# Input_Power.net
KiCad netlist of a schematic drawn in Altium Designer
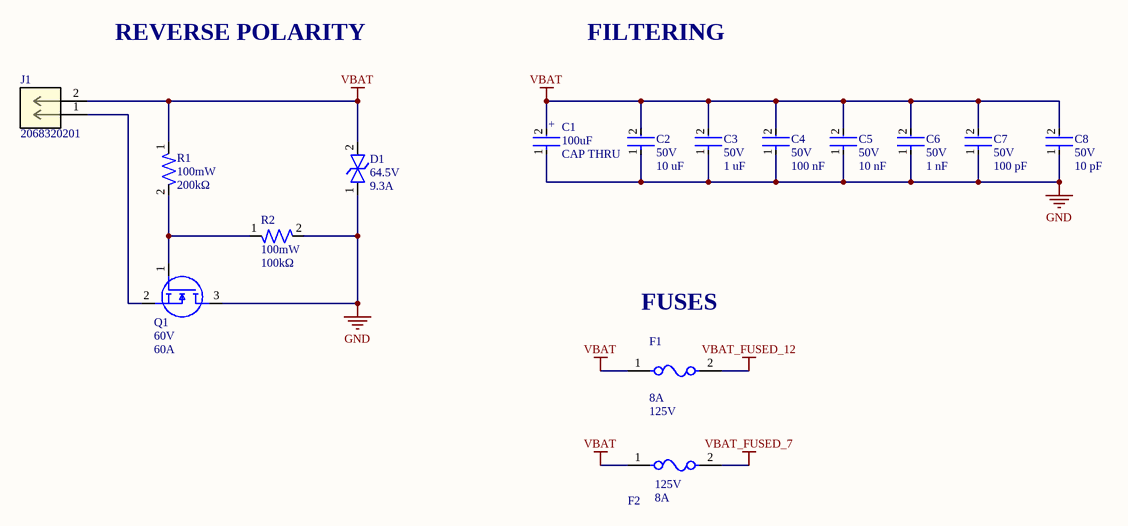
[diagram p0: Input Power.SchDoc]

(export (version "E")
  (design (tool "Eeschema 10.0.6"))
  (components
    (comp (ref "C1")
      (value "CAP THRU")
      (footprint "WCAP-ATUL_8X11.5(DXL)")
      (fields
        (field (name "MF") "{'manufacturer': u'~{W}xfcrth Elektronik'}")
        (field (name "MP") "860040674004")
        (field (name "ALTIUM_VALUE") "100uF")
      )
      (libsource (lib "EHW_27") (part "CAP THRU"))
    )
    (comp (ref "C2")
      (value "CAP 1210")
      (footprint "CAP-1210")
      (fields (field (name "VOLTAGE RATING") "50V") (field (name "CAPACITANCE") "10 uF"))
      (libsource (lib "EHW_27") (part "CAP 1210"))
    )
    (comp (ref "C3")
      (value "CAP 1210")
      (footprint "CAP-1210")
      (fields (field (name "VOLTAGE RATING") "50V") (field (name "CAPACITANCE") "1 uF"))
      (libsource (lib "EHW_27") (part "CAP 1210"))
    )
    (comp (ref "C4")
      (value "CAP 1210")
      (footprint "CAP-1210")
      (fields (field (name "VOLTAGE RATING") "50V") (field (name "CAPACITANCE") "100 nF"))
      (libsource (lib "EHW_27") (part "CAP 1210"))
    )
    (comp (ref "C5")
      (value "CAP 1210")
      (footprint "CAP-1210")
      (fields (field (name "VOLTAGE RATING") "50V") (field (name "CAPACITANCE") "10 nF"))
      (libsource (lib "EHW_27") (part "CAP 1210"))
    )
    (comp (ref "C6")
      (value "CAP 1210")
      (footprint "CAP-1210")
      (fields (field (name "VOLTAGE RATING") "50V") (field (name "CAPACITANCE") "1 nF"))
      (libsource (lib "EHW_27") (part "CAP 1210"))
    )
    (comp (ref "C7")
      (value "CAP 1210")
      (footprint "CAP-1210")
      (fields (field (name "VOLTAGE RATING") "50V") (field (name "CAPACITANCE") "100 pF"))
      (libsource (lib "EHW_27") (part "CAP 1210"))
    )
    (comp (ref "C8")
      (value "CAP 1210")
      (footprint "CAP-1210")
      (fields (field (name "VOLTAGE RATING") "50V") (field (name "CAPACITANCE") "10 pF"))
      (libsource (lib "EHW_27") (part "CAP 1210"))
    )
    (comp (ref "D1")
      (value "SMBJ40CA")
      (footprint "DO-214AA (SMBJ)")
      (description "TVS DIODE 40VWM 64.5VC DO214AA")
      (fields (field (name "VOLTAGE RATING") "64.5V") (field (name "CURRENT RATING") "9.3A"))
      (libsource (lib "EHW_27") (part "DIO-TVS-0001"))
    )
    (comp (ref "F1")
      (value "01550900M")
      (footprint "FUSE-0001")
      (description "FUSE BLOK CARTRIDGE 125V 10A SMD")
      (fields (field (name "FUSE CURRENT") "8A") (field (name "VOLTAGE RATING") "125V"))
      (libsource (lib "EHW_27") (part "FUSE-0001"))
    )
    (comp (ref "F2")
      (value "01550900M")
      (footprint "FUSE-0001")
      (description "FUSE BLOK CARTRIDGE 125V 10A SMD")
      (fields (field (name "FUSE CURRENT") "8A") (field (name "VOLTAGE RATING") "125V"))
      (libsource (lib "Altium Content Vault") (part "FUSE-0001"))
    )
    (comp (ref "J1")
      (value "2068320201")
      (footprint "CONN_2068320000-SD_02_MOL")
      (fields (field (name "COPYRIGHT") "Copyright (C) 2025 Ultra Librarian. All rights reserved."))
      (libsource (lib "EHW_27") (part "CONN MF+ 2 PIN VERT"))
    )
    (comp (ref "Q1")
      (value "CSD18543Q3AT")
      (footprint "IC-8VSONCLIP")
      (description "MOSFET N-CH 60V 12A/60A 8VSON")
      (fields (field (name "VOLTAGE") "60V") (field (name "CONTINUOUS CURRENT") "60A"))
      (libsource (lib "EHW_27") (part "NMOS-60A-0001"))
    )
    (comp (ref "R1")
      (value "RES 0805")
      (footprint "RES-0805")
      (fields (field (name "WATTAGE") "100mW") (field (name "RESISTANCE") "200kΩ"))
      (libsource (lib "EHW_27") (part "RES 0805"))
    )
    (comp (ref "R2")
      (value "RES 0805")
      (footprint "RES-0805")
      (fields (field (name "WATTAGE") "100mW") (field (name "RESISTANCE") "100kΩ"))
      (libsource (lib "EHW_27") (part "RES 0805"))
    )
  )
  (nets
    (net (code "1") (name "GND") (class "Default")
      (node (ref "C1") (pin "1") (pinfunction "1_1") (pintype "passive"))
      (node (ref "C2") (pin "1") (pinfunction "1_1") (pintype "passive"))
      (node (ref "C3") (pin "1") (pinfunction "1_1") (pintype "passive"))
      (node (ref "C4") (pin "1") (pinfunction "1_1") (pintype "passive"))
      (node (ref "C5") (pin "1") (pinfunction "1_1") (pintype "passive"))
      (node (ref "C6") (pin "1") (pinfunction "1_1") (pintype "passive"))
      (node (ref "C7") (pin "1") (pinfunction "1_1") (pintype "passive"))
      (node (ref "C8") (pin "1") (pinfunction "1_1") (pintype "passive"))
      (node (ref "D1") (pin "1") (pintype "passive"))
      (node (ref "Q1") (pin "3") (pinfunction "D_3") (pintype "passive"))
      (node (ref "R2") (pin "2") (pinfunction "2_2") (pintype "passive"))
    )
    (net (code "2") (name "Net-(Q1-G)") (class "Default")
      (node (ref "Q1") (pin "1") (pinfunction "G_1") (pintype "passive"))
      (node (ref "R1") (pin "2") (pinfunction "2_2") (pintype "passive"))
      (node (ref "R2") (pin "1") (pinfunction "1_1") (pintype "passive"))
    )
    (net (code "3") (name "Net-(Q1-S)") (class "Default")
      (node (ref "J1") (pin "1") (pinfunction "1_1") (pintype "passive"))
      (node (ref "Q1") (pin "2") (pinfunction "S_2") (pintype "passive"))
    )
    (net (code "4") (name "VBAT") (class "Default")
      (node (ref "C1") (pin "2") (pinfunction "2_2") (pintype "passive"))
      (node (ref "C2") (pin "2") (pinfunction "2_2") (pintype "passive"))
      (node (ref "C3") (pin "2") (pinfunction "2_2") (pintype "passive"))
      (node (ref "C4") (pin "2") (pinfunction "2_2") (pintype "passive"))
      (node (ref "C5") (pin "2") (pinfunction "2_2") (pintype "passive"))
      (node (ref "C6") (pin "2") (pinfunction "2_2") (pintype "passive"))
      (node (ref "C7") (pin "2") (pinfunction "2_2") (pintype "passive"))
      (node (ref "C8") (pin "2") (pinfunction "2_2") (pintype "passive"))
      (node (ref "D1") (pin "2") (pintype "passive"))
      (node (ref "F1") (pin "1") (pinfunction "1_1") (pintype "passive"))
      (node (ref "F2") (pin "1") (pinfunction "1_1") (pintype "passive"))
      (node (ref "J1") (pin "2") (pinfunction "2_2") (pintype "passive"))
      (node (ref "R1") (pin "1") (pinfunction "1_1") (pintype "passive"))
    )
    (net (code "5") (name "VBAT_FUSED_7") (class "Default")
      (node (ref "F2") (pin "2") (pinfunction "2_2") (pintype "passive"))
    )
    (net (code "6") (name "VBAT_FUSED_12") (class "Default")
      (node (ref "F1") (pin "2") (pinfunction "2_2") (pintype "passive"))
    )
  )
)
